# Workshop_Schematic.net
KiCad netlist of a schematic drawn in Altium Designer
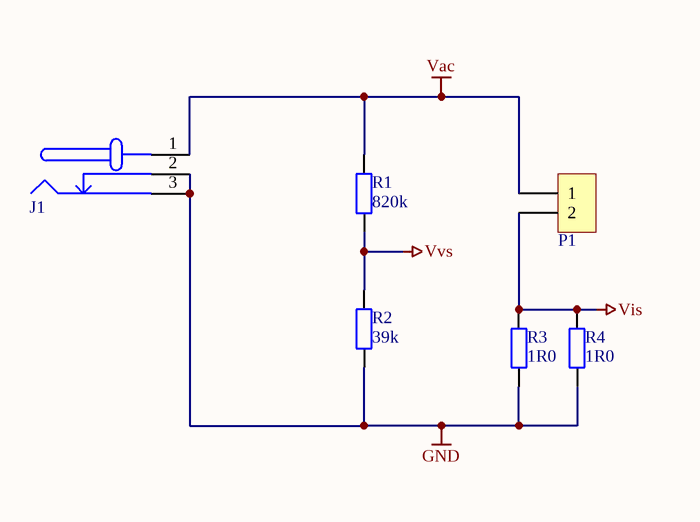
[diagram p0: Workshop_Schematic.SchDoc]

(export (version "E")
  (design (tool "Eeschema 10.0.6"))
  (components
    (comp (ref "J1")
      (value "DC barrel jack")
      (footprint "AC-Socket")
      (description "DC barrel jack connection to AC source")
      (libsource (lib "EE209_Library") (part "AC_Input"))
    )
    (comp (ref "P1")
      (value "Dual Banana Plugs")
      (footprint "Dual Banana Plug")
      (description "Dual banana plugs connection to the AC load")
      (fields (field (name "PUBLISHER") "Altium Limited"))
      (libsource (lib "EE209_Library") (part "AC_Output"))
    )
    (comp (ref "R1")
      (value "820k")
      (footprint "AXIAL-0.4")
      (description "Through hole resistor")
      (fields (field (name "PUBLISHER") "Altium Limited"))
      (libsource (lib "EE209_Library") (part "Res_TH_0AX4"))
    )
    (comp (ref "R2")
      (value "39k")
      (footprint "AXIAL-0.4")
      (description "Through hole resistor")
      (fields (field (name "PUBLISHER") "Altium Limited"))
      (libsource (lib "EE209_Library") (part "Res_TH_0AX4"))
    )
    (comp (ref "R3")
      (value "1R0")
      (footprint "AXIAL-0.4")
      (description "Through hole resistor")
      (fields (field (name "PUBLISHER") "Altium Limited"))
      (libsource (lib "EE209_Library") (part "Res_TH_0AX4"))
    )
    (comp (ref "R4")
      (value "1R0")
      (footprint "AXIAL-0.4")
      (description "Through hole resistor")
      (fields (field (name "PUBLISHER") "Altium Limited"))
      (libsource (lib "EE209_Library") (part "Res_TH_0AX4"))
    )
  )
  (nets
    (net (code "1") (name "GND") (class "Default")
      (node (ref "J1") (pin "2") (pinfunction "GND_ALT_2") (pintype "power_in"))
      (node (ref "J1") (pin "3") (pinfunction "GND_3") (pintype "power_in"))
      (node (ref "R2") (pin "1") (pinfunction "1_1") (pintype "passive"))
      (node (ref "R3") (pin "1") (pinfunction "1_1") (pintype "passive"))
      (node (ref "R4") (pin "1") (pinfunction "1_1") (pintype "passive"))
    )
    (net (code "2") (name "Vac") (class "Default")
      (node (ref "J1") (pin "1") (pinfunction "VCC_1") (pintype "power_in"))
      (node (ref "P1") (pin "1") (pinfunction "1_1") (pintype "passive"))
      (node (ref "R1") (pin "2") (pinfunction "2_2") (pintype "passive"))
    )
    (net (code "3") (name "Vis") (class "Default")
      (node (ref "P1") (pin "2") (pinfunction "2_2") (pintype "passive"))
      (node (ref "R3") (pin "2") (pinfunction "2_2") (pintype "passive"))
      (node (ref "R4") (pin "2") (pinfunction "2_2") (pintype "passive"))
    )
    (net (code "4") (name "Vvs") (class "Default")
      (node (ref "R1") (pin "1") (pinfunction "1_1") (pintype "passive"))
      (node (ref "R2") (pin "2") (pinfunction "2_2") (pintype "passive"))
    )
  )
)
